# R141E.net
KiCad netlist of a schematic drawn in EAGLE
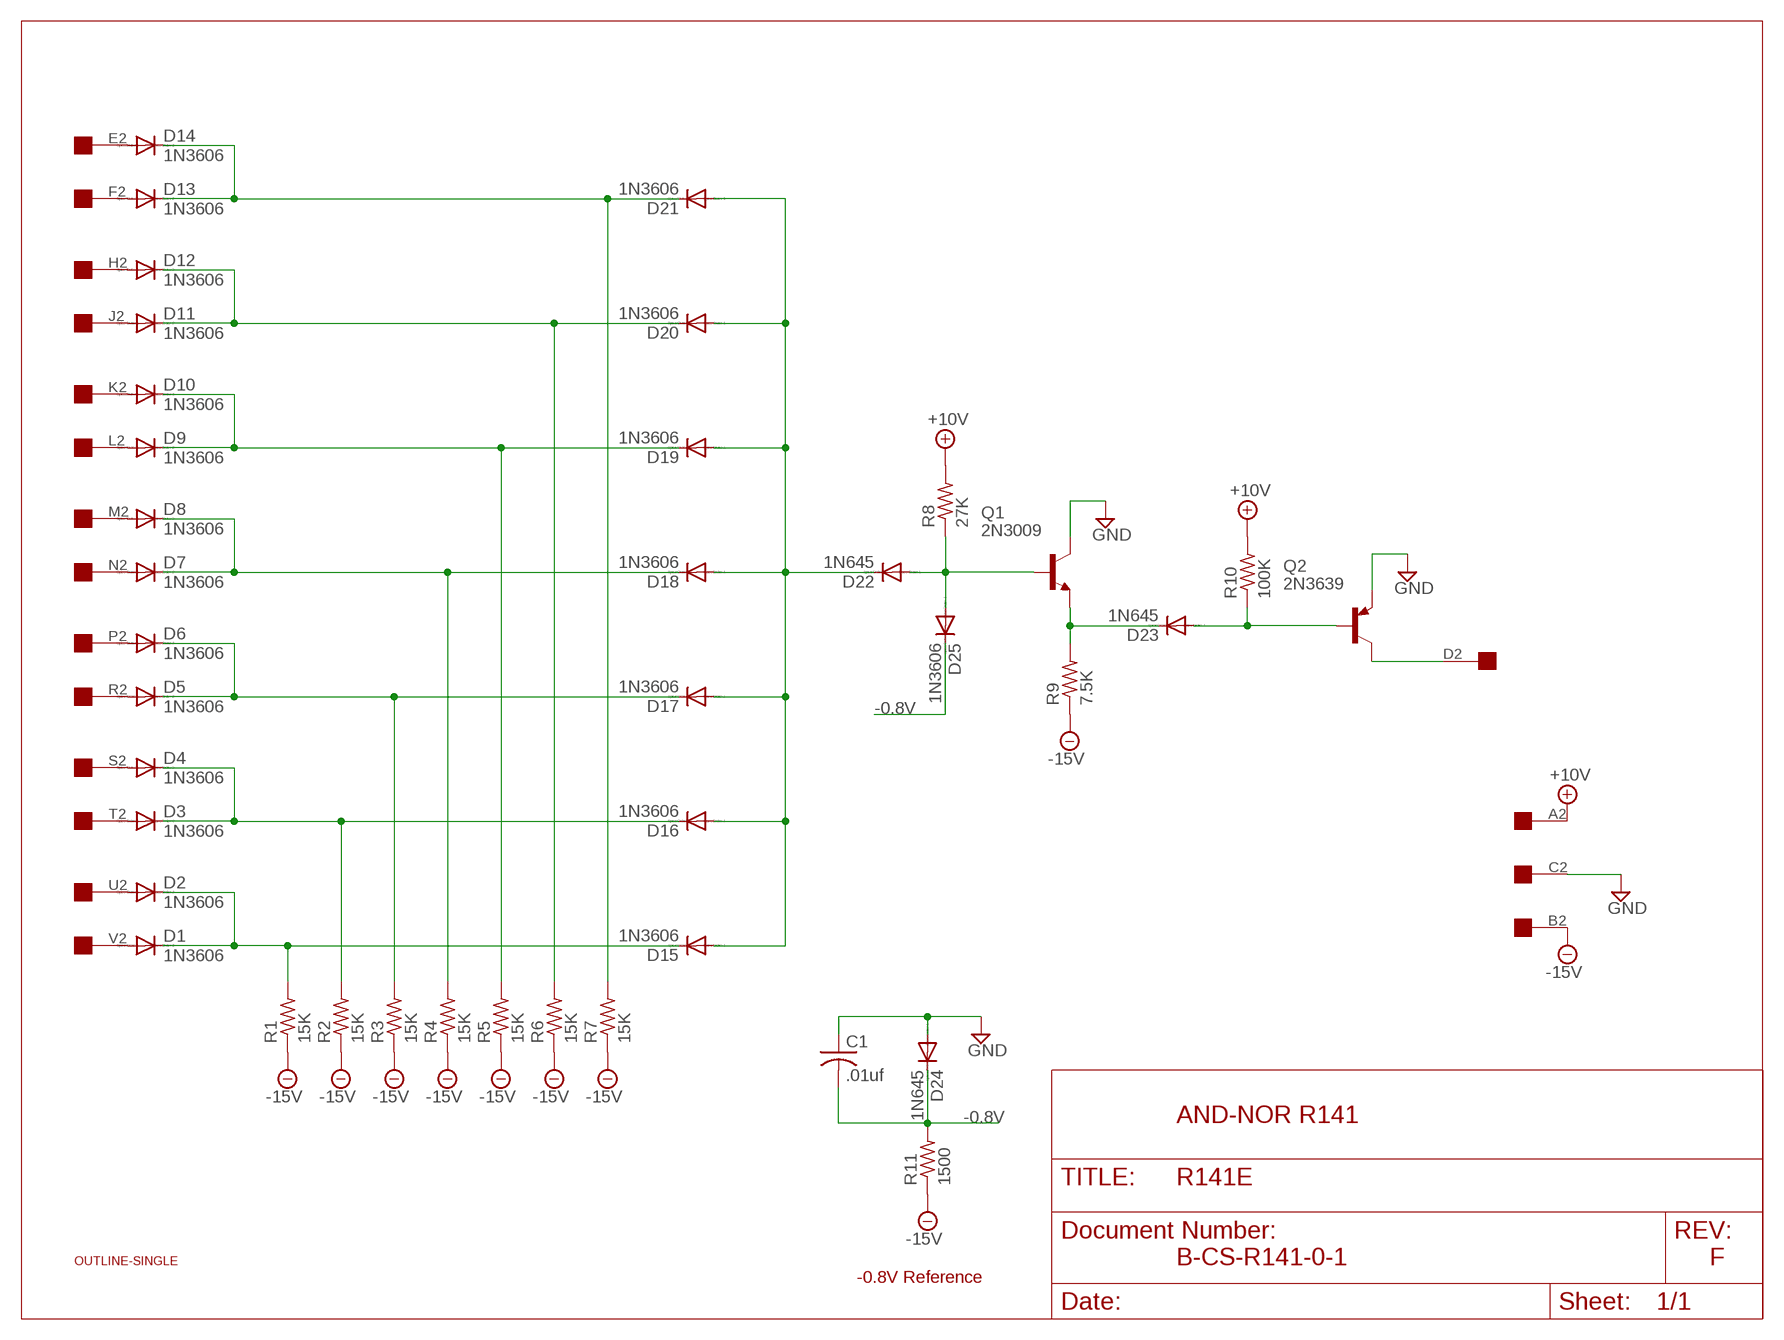
[diagram p0: schematic, sheet 1]

(export (version "E")
  (design (tool "Eeschema 10.0.6"))
  (components
    (comp (ref "C1")
      (value ".01uf")
      (footprint "eagle-import:C050-025X075")
      (libsource (lib "eagle-import") (part "C-US050-025X075"))
    )
    (comp (ref "D1")
      (value "1N3606")
      (footprint "eagle-import:DO35-10")
      (libsource (lib "eagle-import") (part "1N4148DO35-10"))
    )
    (comp (ref "D2")
      (value "1N3606")
      (footprint "eagle-import:DO35-10")
      (libsource (lib "eagle-import") (part "1N4148DO35-10"))
    )
    (comp (ref "D3")
      (value "1N3606")
      (footprint "eagle-import:DO35-10")
      (libsource (lib "eagle-import") (part "1N4148DO35-10"))
    )
    (comp (ref "D4")
      (value "1N3606")
      (footprint "eagle-import:DO35-10")
      (libsource (lib "eagle-import") (part "1N4148DO35-10"))
    )
    (comp (ref "D5")
      (value "1N3606")
      (footprint "eagle-import:DO35-10")
      (libsource (lib "eagle-import") (part "1N4148DO35-10"))
    )
    (comp (ref "D6")
      (value "1N3606")
      (footprint "eagle-import:DO35-10")
      (libsource (lib "eagle-import") (part "1N4148DO35-10"))
    )
    (comp (ref "D7")
      (value "1N3606")
      (footprint "eagle-import:DO35-10")
      (libsource (lib "eagle-import") (part "1N4148DO35-10"))
    )
    (comp (ref "D8")
      (value "1N3606")
      (footprint "eagle-import:DO35-10")
      (libsource (lib "eagle-import") (part "1N4148DO35-10"))
    )
    (comp (ref "D9")
      (value "1N3606")
      (footprint "eagle-import:DO35-10")
      (libsource (lib "eagle-import") (part "1N4148DO35-10"))
    )
    (comp (ref "D10")
      (value "1N3606")
      (footprint "eagle-import:DO35-10")
      (libsource (lib "eagle-import") (part "1N4148DO35-10"))
    )
    (comp (ref "D11")
      (value "1N3606")
      (footprint "eagle-import:DO35-10")
      (libsource (lib "eagle-import") (part "1N4148DO35-10"))
    )
    (comp (ref "D12")
      (value "1N3606")
      (footprint "eagle-import:DO35-10")
      (libsource (lib "eagle-import") (part "1N4148DO35-10"))
    )
    (comp (ref "D13")
      (value "1N3606")
      (footprint "eagle-import:DO35-10")
      (libsource (lib "eagle-import") (part "1N4148DO35-10"))
    )
    (comp (ref "D14")
      (value "1N3606")
      (footprint "eagle-import:DO35-10")
      (libsource (lib "eagle-import") (part "1N4148DO35-10"))
    )
    (comp (ref "D15")
      (value "1N3606")
      (footprint "eagle-import:DO35-10")
      (libsource (lib "eagle-import") (part "1N4148DO35-10"))
    )
    (comp (ref "D16")
      (value "1N3606")
      (footprint "eagle-import:DO35-10")
      (libsource (lib "eagle-import") (part "1N4148DO35-10"))
    )
    (comp (ref "D17")
      (value "1N3606")
      (footprint "eagle-import:DO35-10")
      (libsource (lib "eagle-import") (part "1N4148DO35-10"))
    )
    (comp (ref "D18")
      (value "1N3606")
      (footprint "eagle-import:DO35-10")
      (libsource (lib "eagle-import") (part "1N4148DO35-10"))
    )
    (comp (ref "D19")
      (value "1N3606")
      (footprint "eagle-import:DO35-10")
      (libsource (lib "eagle-import") (part "1N4148DO35-10"))
    )
    (comp (ref "D20")
      (value "1N3606")
      (footprint "eagle-import:DO35-10")
      (libsource (lib "eagle-import") (part "1N4148DO35-10"))
    )
    (comp (ref "D21")
      (value "1N3606")
      (footprint "eagle-import:DO35-10")
      (libsource (lib "eagle-import") (part "1N4148DO35-10"))
    )
    (comp (ref "D22")
      (value "1N645")
      (footprint "eagle-import:DO35-10")
      (libsource (lib "eagle-import") (part "1N4148DO35-10"))
    )
    (comp (ref "D23")
      (value "1N645")
      (footprint "eagle-import:DO35-10")
      (libsource (lib "eagle-import") (part "1N4148DO35-10"))
    )
    (comp (ref "D24")
      (value "1N645")
      (footprint "eagle-import:DO35-10")
      (libsource (lib "eagle-import") (part "1N4148DO35-10"))
    )
    (comp (ref "D25")
      (value "1N3606")
      (footprint "eagle-import:DO35-10")
      (libsource (lib "eagle-import") (part "1N4148DO35-10"))
    )
    (comp (ref "Q1")
      (value "2N3009")
      (footprint "eagle-import:TO39")
      (libsource (lib "eagle-import") (part "-NPN-TO39-EBC2N3019"))
    )
    (comp (ref "Q2")
      (value "2N3639")
      (footprint "eagle-import:TO39")
      (libsource (lib "eagle-import") (part "2N3637"))
    )
    (comp (ref "R1")
      (value "15K")
      (footprint "eagle-import:0207_10")
      (libsource (lib "eagle-import") (part "R-US_0207/10"))
    )
    (comp (ref "R2")
      (value "15K")
      (footprint "eagle-import:0207_10")
      (libsource (lib "eagle-import") (part "R-US_0207/10"))
    )
    (comp (ref "R3")
      (value "15K")
      (footprint "eagle-import:0207_10")
      (libsource (lib "eagle-import") (part "R-US_0207/10"))
    )
    (comp (ref "R4")
      (value "15K")
      (footprint "eagle-import:0207_10")
      (libsource (lib "eagle-import") (part "R-US_0207/10"))
    )
    (comp (ref "R5")
      (value "15K")
      (footprint "eagle-import:0207_10")
      (libsource (lib "eagle-import") (part "R-US_0207/10"))
    )
    (comp (ref "R6")
      (value "15K")
      (footprint "eagle-import:0207_10")
      (libsource (lib "eagle-import") (part "R-US_0207/10"))
    )
    (comp (ref "R7")
      (value "15K")
      (footprint "eagle-import:0207_10")
      (libsource (lib "eagle-import") (part "R-US_0207/10"))
    )
    (comp (ref "R8")
      (value "27K")
      (footprint "eagle-import:0207_10")
      (libsource (lib "eagle-import") (part "R-US_0207/10"))
    )
    (comp (ref "R9")
      (value "7.5K")
      (footprint "eagle-import:0207_10")
      (libsource (lib "eagle-import") (part "R-US_0207/10"))
    )
    (comp (ref "R10")
      (value "100K")
      (footprint "eagle-import:0207_10")
      (libsource (lib "eagle-import") (part "R-US_0207/10"))
    )
    (comp (ref "R11")
      (value "1500")
      (footprint "eagle-import:0207_10")
      (libsource (lib "eagle-import") (part "R-US_0207/10"))
    )
    (comp (ref "U$1")
      (value "OUTLINE-SINGLE")
      (footprint "eagle-import:SINGLE")
      (libsource (lib "eagle-import") (part "OUTLINE-SINGLE"))
    )
    (comp (ref "U$2")
      (value "EDGE-1")
      (footprint "eagle-import:EDGE-CON1")
      (libsource (lib "eagle-import") (part "EDGE-1"))
    )
  )
  (nets
    (net (code "1") (name "+10V") (class "Default")
      (node (ref "R10") (pin "2") (pinfunction "2_2") (pintype "passive"))
      (node (ref "R8") (pin "2") (pinfunction "2_2") (pintype "passive"))
      (node (ref "U$2") (pin "A2") (pinfunction "1_A2") (pintype "bidirectional"))
    )
    (net (code "2") (name "-15V") (class "Default")
      (node (ref "R1") (pin "1") (pinfunction "1_1") (pintype "passive"))
      (node (ref "R11") (pin "1") (pinfunction "1_1") (pintype "passive"))
      (node (ref "R2") (pin "1") (pinfunction "1_1") (pintype "passive"))
      (node (ref "R3") (pin "1") (pinfunction "1_1") (pintype "passive"))
      (node (ref "R4") (pin "1") (pinfunction "1_1") (pintype "passive"))
      (node (ref "R5") (pin "1") (pinfunction "1_1") (pintype "passive"))
      (node (ref "R6") (pin "1") (pinfunction "1_1") (pintype "passive"))
      (node (ref "R7") (pin "1") (pinfunction "1_1") (pintype "passive"))
      (node (ref "R9") (pin "1") (pinfunction "1_1") (pintype "passive"))
      (node (ref "U$2") (pin "B2") (pinfunction "1_B2") (pintype "bidirectional"))
    )
    (net (code "3") (name "/-0.8V") (class "Default")
      (node (ref "C1") (pin "2") (pinfunction "2_2") (pintype "passive"))
      (node (ref "D24") (pin "C") (pinfunction "C_C") (pintype "passive"))
      (node (ref "D25") (pin "C") (pinfunction "C_C") (pintype "passive"))
      (node (ref "R11") (pin "2") (pinfunction "2_2") (pintype "passive"))
    )
    (net (code "4") (name "GND") (class "Default")
      (node (ref "C1") (pin "1") (pinfunction "1_1") (pintype "passive"))
      (node (ref "D24") (pin "A") (pinfunction "A_A") (pintype "passive"))
      (node (ref "Q1") (pin "3") (pinfunction "C_3") (pintype "passive"))
      (node (ref "Q2") (pin "1") (pinfunction "E_1") (pintype "passive"))
      (node (ref "U$2") (pin "C2") (pinfunction "1_C2") (pintype "bidirectional"))
    )
    (net (code "5") (name "Net-(D1-PadC)") (class "Default")
      (node (ref "D1") (pin "C") (pinfunction "C_C") (pintype "passive"))
      (node (ref "D15") (pin "C") (pinfunction "C_C") (pintype "passive"))
      (node (ref "D2") (pin "C") (pinfunction "C_C") (pintype "passive"))
      (node (ref "R1") (pin "2") (pinfunction "2_2") (pintype "passive"))
    )
    (net (code "6") (name "Net-(D10-PadC)") (class "Default")
      (node (ref "D10") (pin "C") (pinfunction "C_C") (pintype "passive"))
      (node (ref "D19") (pin "C") (pinfunction "C_C") (pintype "passive"))
      (node (ref "D9") (pin "C") (pinfunction "C_C") (pintype "passive"))
      (node (ref "R5") (pin "2") (pinfunction "2_2") (pintype "passive"))
    )
    (net (code "7") (name "Net-(D11-PadC)") (class "Default")
      (node (ref "D11") (pin "C") (pinfunction "C_C") (pintype "passive"))
      (node (ref "D12") (pin "C") (pinfunction "C_C") (pintype "passive"))
      (node (ref "D20") (pin "C") (pinfunction "C_C") (pintype "passive"))
      (node (ref "R6") (pin "2") (pinfunction "2_2") (pintype "passive"))
    )
    (net (code "8") (name "Net-(D13-PadC)") (class "Default")
      (node (ref "D13") (pin "C") (pinfunction "C_C") (pintype "passive"))
      (node (ref "D14") (pin "C") (pinfunction "C_C") (pintype "passive"))
      (node (ref "D21") (pin "C") (pinfunction "C_C") (pintype "passive"))
      (node (ref "R7") (pin "2") (pinfunction "2_2") (pintype "passive"))
    )
    (net (code "9") (name "Net-(D15-PadA)") (class "Default")
      (node (ref "D15") (pin "A") (pinfunction "A_A") (pintype "passive"))
      (node (ref "D16") (pin "A") (pinfunction "A_A") (pintype "passive"))
      (node (ref "D17") (pin "A") (pinfunction "A_A") (pintype "passive"))
      (node (ref "D18") (pin "A") (pinfunction "A_A") (pintype "passive"))
      (node (ref "D19") (pin "A") (pinfunction "A_A") (pintype "passive"))
      (node (ref "D20") (pin "A") (pinfunction "A_A") (pintype "passive"))
      (node (ref "D21") (pin "A") (pinfunction "A_A") (pintype "passive"))
      (node (ref "D22") (pin "C") (pinfunction "C_C") (pintype "passive"))
    )
    (net (code "10") (name "Net-(D16-PadC)") (class "Default")
      (node (ref "D16") (pin "C") (pinfunction "C_C") (pintype "passive"))
      (node (ref "D3") (pin "C") (pinfunction "C_C") (pintype "passive"))
      (node (ref "D4") (pin "C") (pinfunction "C_C") (pintype "passive"))
      (node (ref "R2") (pin "2") (pinfunction "2_2") (pintype "passive"))
    )
    (net (code "11") (name "Net-(D17-PadC)") (class "Default")
      (node (ref "D17") (pin "C") (pinfunction "C_C") (pintype "passive"))
      (node (ref "D5") (pin "C") (pinfunction "C_C") (pintype "passive"))
      (node (ref "D6") (pin "C") (pinfunction "C_C") (pintype "passive"))
      (node (ref "R3") (pin "2") (pinfunction "2_2") (pintype "passive"))
    )
    (net (code "12") (name "Net-(D18-PadC)") (class "Default")
      (node (ref "D18") (pin "C") (pinfunction "C_C") (pintype "passive"))
      (node (ref "D7") (pin "C") (pinfunction "C_C") (pintype "passive"))
      (node (ref "D8") (pin "C") (pinfunction "C_C") (pintype "passive"))
      (node (ref "R4") (pin "2") (pinfunction "2_2") (pintype "passive"))
    )
    (net (code "13") (name "Net-(Q1-B)") (class "Default")
      (node (ref "D22") (pin "A") (pinfunction "A_A") (pintype "passive"))
      (node (ref "D25") (pin "A") (pinfunction "A_A") (pintype "passive"))
      (node (ref "Q1") (pin "2") (pinfunction "B_2") (pintype "passive"))
      (node (ref "R8") (pin "1") (pinfunction "1_1") (pintype "passive"))
    )
    (net (code "14") (name "Net-(Q1-E)") (class "Default")
      (node (ref "D23") (pin "C") (pinfunction "C_C") (pintype "passive"))
      (node (ref "Q1") (pin "1") (pinfunction "E_1") (pintype "passive"))
      (node (ref "R9") (pin "2") (pinfunction "2_2") (pintype "passive"))
    )
    (net (code "15") (name "Net-(Q2-B)") (class "Default")
      (node (ref "D23") (pin "A") (pinfunction "A_A") (pintype "passive"))
      (node (ref "Q2") (pin "2") (pinfunction "B_2") (pintype "passive"))
      (node (ref "R10") (pin "1") (pinfunction "1_1") (pintype "passive"))
    )
    (net (code "16") (name "Net-(Q2-C)") (class "Default")
      (node (ref "Q2") (pin "3") (pinfunction "C_3") (pintype "passive"))
      (node (ref "U$2") (pin "D2") (pinfunction "1_D2") (pintype "bidirectional"))
    )
    (net (code "17") (name "Net-(U$2E-1)") (class "Default")
      (node (ref "D14") (pin "A") (pinfunction "A_A") (pintype "passive"))
      (node (ref "U$2") (pin "E2") (pinfunction "1_E2") (pintype "bidirectional"))
    )
    (net (code "18") (name "Net-(U$2F-1)") (class "Default")
      (node (ref "D13") (pin "A") (pinfunction "A_A") (pintype "passive"))
      (node (ref "U$2") (pin "F2") (pinfunction "1_F2") (pintype "bidirectional"))
    )
    (net (code "19") (name "Net-(U$2G-1)") (class "Default")
      (node (ref "D12") (pin "A") (pinfunction "A_A") (pintype "passive"))
      (node (ref "U$2") (pin "H2") (pinfunction "1_H2") (pintype "bidirectional"))
    )
    (net (code "20") (name "Net-(U$2H-1)") (class "Default")
      (node (ref "D11") (pin "A") (pinfunction "A_A") (pintype "passive"))
      (node (ref "U$2") (pin "J2") (pinfunction "1_J2") (pintype "bidirectional"))
    )
    (net (code "21") (name "Net-(U$2I-1)") (class "Default")
      (node (ref "D10") (pin "A") (pinfunction "A_A") (pintype "passive"))
      (node (ref "U$2") (pin "K2") (pinfunction "1_K2") (pintype "bidirectional"))
    )
    (net (code "22") (name "Net-(U$2J-1)") (class "Default")
      (node (ref "D9") (pin "A") (pinfunction "A_A") (pintype "passive"))
      (node (ref "U$2") (pin "L2") (pinfunction "1_L2") (pintype "bidirectional"))
    )
    (net (code "23") (name "Net-(U$2K-1)") (class "Default")
      (node (ref "D8") (pin "A") (pinfunction "A_A") (pintype "passive"))
      (node (ref "U$2") (pin "M2") (pinfunction "1_M2") (pintype "bidirectional"))
    )
    (net (code "24") (name "Net-(U$2L-1)") (class "Default")
      (node (ref "D7") (pin "A") (pinfunction "A_A") (pintype "passive"))
      (node (ref "U$2") (pin "N2") (pinfunction "1_N2") (pintype "bidirectional"))
    )
    (net (code "25") (name "Net-(U$2M-1)") (class "Default")
      (node (ref "D6") (pin "A") (pinfunction "A_A") (pintype "passive"))
      (node (ref "U$2") (pin "P2") (pinfunction "1_P2") (pintype "bidirectional"))
    )
    (net (code "26") (name "Net-(U$2N-1)") (class "Default")
      (node (ref "D5") (pin "A") (pinfunction "A_A") (pintype "passive"))
      (node (ref "U$2") (pin "R2") (pinfunction "1_R2") (pintype "bidirectional"))
    )
    (net (code "27") (name "Net-(U$2O-1)") (class "Default")
      (node (ref "D4") (pin "A") (pinfunction "A_A") (pintype "passive"))
      (node (ref "U$2") (pin "S2") (pinfunction "1_S2") (pintype "bidirectional"))
    )
    (net (code "28") (name "Net-(U$2P-1)") (class "Default")
      (node (ref "D3") (pin "A") (pinfunction "A_A") (pintype "passive"))
      (node (ref "U$2") (pin "T2") (pinfunction "1_T2") (pintype "bidirectional"))
    )
    (net (code "29") (name "Net-(U$2Q-1)") (class "Default")
      (node (ref "D2") (pin "A") (pinfunction "A_A") (pintype "passive"))
      (node (ref "U$2") (pin "U2") (pinfunction "1_U2") (pintype "bidirectional"))
    )
    (net (code "30") (name "Net-(U$2R-1)") (class "Default")
      (node (ref "D1") (pin "A") (pinfunction "A_A") (pintype "passive"))
      (node (ref "U$2") (pin "V2") (pinfunction "1_V2") (pintype "bidirectional"))
    )
  )
)
